# SP1_TYPEC_PWR_IN.net
KiCad netlist of a schematic drawn in Altium Designer
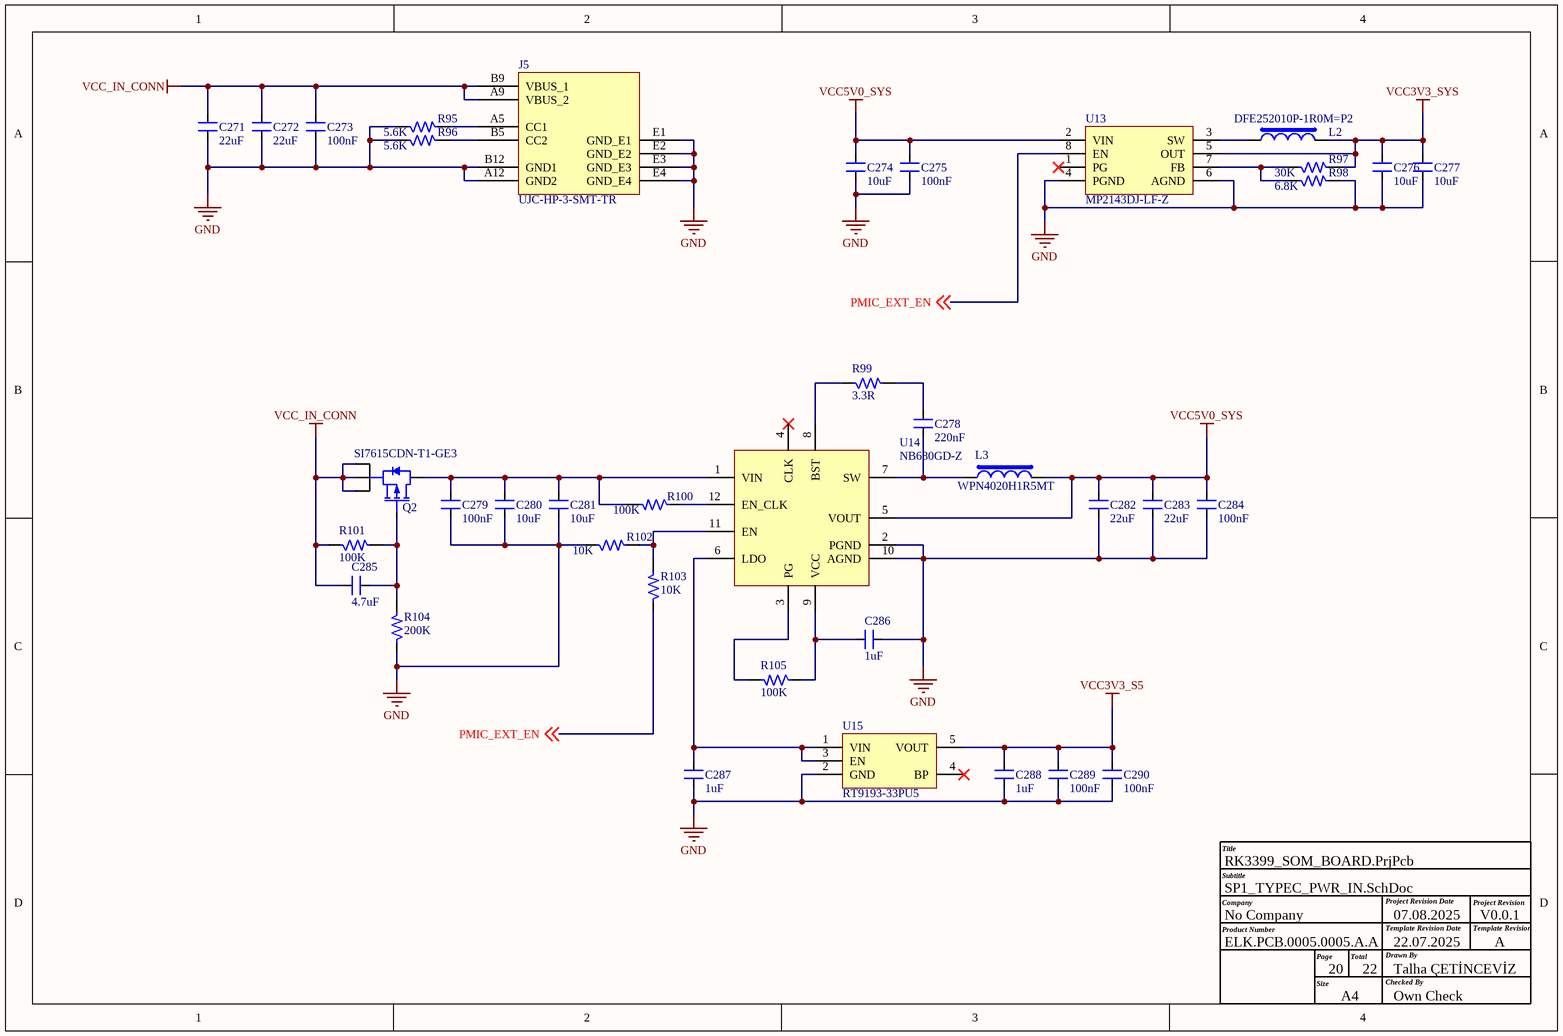
[diagram p0: SP1_TYPEC_PWR_IN.SchDoc]

(export (version "E")
  (design (tool "Eeschema 10.0.6"))
  (components
    (comp (ref "C271")
      (value "22uF")
      (footprint "CAP_0603")
      (description "22µF ±20% 10V Ceramic Capacitor X5R 0603 (1608 Metric)")
      (fields
        (field (name "MANUFACTURER") "Murata Electronics")
        (field (name "MANUFACTURER PART NUMBER") "GRM188R61A226ME15D")
      )
      (libsource (lib "EsteemPCB_SOM_Course_intlib") (part "CAP_22uF-10V-20%-0603"))
    )
    (comp (ref "C272")
      (value "22uF")
      (footprint "CAP_0603")
      (description "22µF ±20% 10V Ceramic Capacitor X5R 0603 (1608 Metric)")
      (fields
        (field (name "MANUFACTURER") "Murata Electronics")
        (field (name "MANUFACTURER PART NUMBER") "GRM188R61A226ME15D")
      )
      (libsource (lib "EsteemPCB_SOM_Course_intlib") (part "CAP_22uF-10V-20%-0603"))
    )
    (comp (ref "C273")
      (value "100nF")
      (footprint "CAP_0402")
      (description "0.1µF ±10% 25V Ceramic Capacitor X7R 0402 (1005 Metric)")
      (fields
        (field (name "MANUFACTURER") "Walsin Technology Corporation")
        (field (name "MANUFACTURER PART NUMBER") "0402B104K250CT")
      )
      (libsource (lib "EsteemPCB_SOM_Course_intlib") (part "CAP_100nF-25V-10%-0402"))
    )
    (comp (ref "C274")
      (value "10uF")
      (footprint "CAP_0402")
      (description "10µF ±20% 10V Ceramic Capacitor X5R 0402 (1005 Metric)")
      (fields
        (field (name "MANUFACTURER PART NUMBER") "CL05A106MP5NUNC")
        (field (name "MANUFACTURER") "Samsung Electro-Mechanics")
      )
      (libsource (lib "EsteemPCB_SOM_Course_intlib") (part "CAP_10uF-10V-20%-0402"))
    )
    (comp (ref "C275")
      (value "100nF")
      (footprint "CAP_0402")
      (description "0.1µF ±10% 25V Ceramic Capacitor X7R 0402 (1005 Metric)")
      (fields
        (field (name "MANUFACTURER") "Walsin Technology Corporation")
        (field (name "MANUFACTURER PART NUMBER") "0402B104K250CT")
      )
      (libsource (lib "EsteemPCB_SOM_Course_intlib") (part "CAP_100nF-25V-10%-0402"))
    )
    (comp (ref "C276")
      (value "10uF")
      (footprint "CAP_0402")
      (description "10µF ±20% 10V Ceramic Capacitor X5R 0402 (1005 Metric)")
      (fields
        (field (name "MANUFACTURER PART NUMBER") "CL05A106MP5NUNC")
        (field (name "MANUFACTURER") "Samsung Electro-Mechanics")
      )
      (libsource (lib "EsteemPCB_SOM_Course_intlib") (part "CAP_10uF-10V-20%-0402"))
    )
    (comp (ref "C277")
      (value "10uF")
      (footprint "CAP_0402")
      (description "10µF ±20% 10V Ceramic Capacitor X5R 0402 (1005 Metric)")
      (fields
        (field (name "MANUFACTURER PART NUMBER") "CL05A106MP5NUNC")
        (field (name "MANUFACTURER") "Samsung Electro-Mechanics")
      )
      (libsource (lib "EsteemPCB_SOM_Course_intlib") (part "CAP_10uF-10V-20%-0402"))
    )
    (comp (ref "C278")
      (value "220nF")
      (footprint "CAP_0402")
      (description "0.22µF ±10% 10V Ceramic Capacitor X7R 0402 (1005 Metric)")
      (fields
        (field (name "MANUFACTURER") "Samsung Electro-Mechanics")
        (field (name "MANUFACTURER PART NUMBER") "CL05B224KP5NNNC")
      )
      (libsource (lib "EsteemPCB_SOM_Course_intlib") (part "CAP_220nF-10V-10%-0402"))
    )
    (comp (ref "C279")
      (value "100nF")
      (footprint "CAP_0402")
      (description "0.1µF ±10% 25V Ceramic Capacitor X7R 0402 (1005 Metric)")
      (fields
        (field (name "MANUFACTURER") "Walsin Technology Corporation")
        (field (name "MANUFACTURER PART NUMBER") "0402B104K250CT")
      )
      (libsource (lib "EsteemPCB_SOM_Course_intlib") (part "CAP_100nF-25V-10%-0402"))
    )
    (comp (ref "C280")
      (value "10uF")
      (footprint "CAP_0402")
      (description "10µF ±20% 10V Ceramic Capacitor X5R 0402 (1005 Metric)")
      (fields
        (field (name "MANUFACTURER PART NUMBER") "CL05A106MP5NUNC")
        (field (name "MANUFACTURER") "Samsung Electro-Mechanics")
      )
      (libsource (lib "EsteemPCB_SOM_Course_intlib") (part "CAP_10uF-10V-20%-0402"))
    )
    (comp (ref "C281")
      (value "10uF")
      (footprint "CAP_0402")
      (description "10µF ±20% 10V Ceramic Capacitor X5R 0402 (1005 Metric)")
      (fields
        (field (name "MANUFACTURER PART NUMBER") "CL05A106MP5NUNC")
        (field (name "MANUFACTURER") "Samsung Electro-Mechanics")
      )
      (libsource (lib "EsteemPCB_SOM_Course_intlib") (part "CAP_10uF-10V-20%-0402"))
    )
    (comp (ref "C282")
      (value "22uF")
      (footprint "CAP_0603")
      (description "22µF ±20% 10V Ceramic Capacitor X5R 0603 (1608 Metric)")
      (fields
        (field (name "MANUFACTURER") "Murata Electronics")
        (field (name "MANUFACTURER PART NUMBER") "GRM188R61A226ME15D")
      )
      (libsource (lib "EsteemPCB_SOM_Course_intlib") (part "CAP_22uF-10V-20%-0603"))
    )
    (comp (ref "C283")
      (value "22uF")
      (footprint "CAP_0603")
      (description "22µF ±20% 10V Ceramic Capacitor X5R 0603 (1608 Metric)")
      (fields
        (field (name "MANUFACTURER") "Murata Electronics")
        (field (name "MANUFACTURER PART NUMBER") "GRM188R61A226ME15D")
      )
      (libsource (lib "EsteemPCB_SOM_Course_intlib") (part "CAP_22uF-10V-20%-0603"))
    )
    (comp (ref "C284")
      (value "100nF")
      (footprint "CAP_0402")
      (description "0.1µF ±10% 25V Ceramic Capacitor X7R 0402 (1005 Metric)")
      (fields
        (field (name "MANUFACTURER") "Walsin Technology Corporation")
        (field (name "MANUFACTURER PART NUMBER") "0402B104K250CT")
      )
      (libsource (lib "EsteemPCB_SOM_Course_intlib") (part "CAP_100nF-25V-10%-0402"))
    )
    (comp (ref "C285")
      (value "4.7uF")
      (footprint "CAP_0402")
      (description "4.7µF ±10% 10V Ceramic Capacitor X5R 0402 (1005 Metric)")
      (fields
        (field (name "MANUFACTURER") "Samsung Electro-Mechanics")
        (field (name "MANUFACTURER PART NUMBER") "CL05A475KP5NRNC")
      )
      (libsource (lib "EsteemPCB_SOM_Course_intlib") (part "CAP_4.7uF-10V-10%-0402"))
    )
    (comp (ref "C286")
      (value "1uF")
      (footprint "CAP_0402")
      (description "1µF ±10% 16V Ceramic Capacitor X5R 0402 (1005 Metric)")
      (fields
        (field (name "MANUFACTURER") "Knowles Novacap")
        (field (name "MANUFACTURER PART NUMBER") "0402BW105K160YT")
      )
      (libsource (lib "EsteemPCB_SOM_Course_intlib") (part "CAP_1uF-16V-10%-0402"))
    )
    (comp (ref "C287")
      (value "1uF")
      (footprint "CAP_0402")
      (description "1µF ±10% 16V Ceramic Capacitor X5R 0402 (1005 Metric)")
      (fields
        (field (name "MANUFACTURER") "Knowles Novacap")
        (field (name "MANUFACTURER PART NUMBER") "0402BW105K160YT")
      )
      (libsource (lib "EsteemPCB_SOM_Course_intlib") (part "CAP_1uF-16V-10%-0402"))
    )
    (comp (ref "C288")
      (value "1uF")
      (footprint "CAP_0402")
      (description "1µF ±10% 16V Ceramic Capacitor X5R 0402 (1005 Metric)")
      (fields
        (field (name "MANUFACTURER") "Knowles Novacap")
        (field (name "MANUFACTURER PART NUMBER") "0402BW105K160YT")
      )
      (libsource (lib "EsteemPCB_SOM_Course_intlib") (part "CAP_1uF-16V-10%-0402"))
    )
    (comp (ref "C289")
      (value "100nF")
      (footprint "CAP_0402")
      (description "0.1µF ±10% 25V Ceramic Capacitor X7R 0402 (1005 Metric)")
      (fields
        (field (name "MANUFACTURER") "Walsin Technology Corporation")
        (field (name "MANUFACTURER PART NUMBER") "0402B104K250CT")
      )
      (libsource (lib "EsteemPCB_SOM_Course_intlib") (part "CAP_100nF-25V-10%-0402"))
    )
    (comp (ref "C290")
      (value "100nF")
      (footprint "CAP_0402")
      (description "0.1µF ±10% 25V Ceramic Capacitor X7R 0402 (1005 Metric)")
      (fields
        (field (name "MANUFACTURER") "Walsin Technology Corporation")
        (field (name "MANUFACTURER PART NUMBER") "0402B104K250CT")
      )
      (libsource (lib "EsteemPCB_SOM_Course_intlib") (part "CAP_100nF-25V-10%-0402"))
    )
    (comp (ref "J5")
      (value "UJC-HP-3-SMT-TR")
      (footprint "CON6_48.4_UJC-HP-3-SMT-TR")
      (fields (field (name "MANUFACTURER") "CUI Devices"))
      (libsource (lib "EsteemPCB_SOM_Course_intlib") (part "CON-TYPEC_6X1-100-RA-TH"))
    )
    (comp (ref "L2")
      (value "DFE252010P-1R0M=P2")
      (footprint "IND_1008")
      (description "1µH Shielded Wirewound Inductor 3.8A 54mOhm Max 1008 (2520 Metric)")
      (fields (field (name "MANUFACTURER") "Murata Electronics"))
      (libsource (lib "EsteemPCB_SOM_Course_intlib") (part "IND_1uH-3.8A-20%-1008"))
    )
    (comp (ref "L3")
      (value "WPN4020H1R5MT")
      (footprint "IND_1616")
      (fields (field (name "MANUFACTURER") "Sunlord"))
      (libsource (lib "EsteemPCB_SOM_Course_intlib") (part "IND_1.5uH-6A-20%-SMD"))
    )
    (comp (ref "Q2")
      (value "SI7615CDN-T1-GE3")
      (footprint "PowerPAK_1212-8_SMD")
      (description "P-Channel 20V 35A (Tc) 33W (Tc) Surface Mount PowerPAK® 1212-8")
      (fields (field (name "MANUFACTURER") "Vishay Siliconix"))
      (libsource (lib "EsteemPCB_SOM_Course_intlib") (part "MOSFET-P_20V-35A-1212-8"))
    )
    (comp (ref "R95")
      (value "5.6K")
      (footprint "RES_0402")
      (fields
        (field (name "MANUFACTURER") "KOA Speer Electronics, Inc.")
        (field (name "MANUFACTURER PART NUMBER") "RK73H1ETTP5601F")
      )
      (libsource (lib "EsteemPCB_SOM_Course_intlib") (part "RES_5.6K-0.1W-1%-0402"))
    )
    (comp (ref "R96")
      (value "5.6K")
      (footprint "RES_0402")
      (fields
        (field (name "MANUFACTURER") "KOA Speer Electronics, Inc.")
        (field (name "MANUFACTURER PART NUMBER") "RK73H1ETTP5601F")
      )
      (libsource (lib "EsteemPCB_SOM_Course_intlib") (part "RES_5.6K-0.1W-1%-0402"))
    )
    (comp (ref "R97")
      (value "30K")
      (footprint "RES_0402")
      (fields
        (field (name "MANUFACTURER") "KOA Speer Electronics, Inc.")
        (field (name "MANUFACTURER PART NUMBER") "RK73H1ETTP3002F")
      )
      (libsource (lib "EsteemPCB_SOM_Course_intlib") (part "RES_30K-0.1W-1%-0402"))
    )
    (comp (ref "R98")
      (value "6.8K")
      (footprint "RES_0402")
      (description "6.8 kOhms ±1% 0.1W, 1/10W Chip Resistor 0402 (1005 Metric) Anti-Sulfur Thin Film")
      (fields
        (field (name "MANUFACTURER") "Vishay Beyschlag/Draloric/BC Components")
        (field (name "MANUFACTURER PART NUMBER") "MCS04020C6801FE000")
      )
      (libsource (lib "EsteemPCB_SOM_Course_intlib") (part "RES_6.8K-0.1W-1%-0402"))
    )
    (comp (ref "R99")
      (value "3.3R")
      (footprint "RES_0402")
      (fields
        (field (name "MANUFACTURER") "Panasonic Electronic Components")
        (field (name "MANUFACTURER PART NUMBER") "ERJ-U02F3R30X")
      )
      (libsource (lib "EsteemPCB_SOM_Course_intlib") (part "RES_3.3R-0.1W-1%-0402"))
    )
    (comp (ref "R100")
      (value "100K")
      (footprint "RES_0402")
      (description "100 kOhms ±1% 0.1W, 1/10W Chip Resistor 0402 (1005 Metric) Anti-Sulfur Thin Film")
      (fields
        (field (name "MANUFACTURER") "Vishay Beyschlag/Draloric/BC Components")
        (field (name "MANUFACTURER PART NUMBER") "MCS04020C1003FE000")
      )
      (libsource (lib "EsteemPCB_SOM_Course_intlib") (part "RES_100K-0.1W-1%-0402"))
    )
    (comp (ref "R101")
      (value "100K")
      (footprint "RES_0402")
      (description "100 kOhms ±1% 0.1W, 1/10W Chip Resistor 0402 (1005 Metric) Anti-Sulfur Thin Film")
      (fields
        (field (name "MANUFACTURER") "Vishay Beyschlag/Draloric/BC Components")
        (field (name "MANUFACTURER PART NUMBER") "MCS04020C1003FE000")
      )
      (libsource (lib "EsteemPCB_SOM_Course_intlib") (part "RES_100K-0.1W-1%-0402"))
    )
    (comp (ref "R102")
      (value "10K")
      (footprint "RES_0402")
      (description "10 kOhms ±1% 0.1W, 1/10W Chip Resistor 0402 (1005 Metric) Anti-Sulfur Thin Film")
      (fields
        (field (name "MANUFACTURER") "Vishay Beyschlag/Draloric/BC Components")
        (field (name "MANUFACTURER PART NUMBER") "MCS04020C1002FE000")
      )
      (libsource (lib "EsteemPCB_SOM_Course_intlib") (part "RES_10K-0.1W-1%-0402"))
    )
    (comp (ref "R103")
      (value "10K")
      (footprint "RES_0402")
      (description "10 kOhms ±1% 0.1W, 1/10W Chip Resistor 0402 (1005 Metric) Anti-Sulfur Thin Film")
      (fields
        (field (name "MANUFACTURER") "Vishay Beyschlag/Draloric/BC Components")
        (field (name "MANUFACTURER PART NUMBER") "MCS04020C1002FE000")
      )
      (libsource (lib "EsteemPCB_SOM_Course_intlib") (part "RES_10K-0.1W-1%-0402"))
    )
    (comp (ref "R104")
      (value "200K")
      (footprint "RES_0402")
      (description "200 kOhms ±1% 0.1W, 1/10W Chip Resistor 0402 (1005 Metric) Automotive AEC-Q200 Thick Film")
      (fields
        (field (name "MANUFACTURER") "Panasonic Electronic Components")
        (field (name "MANUFACTURER PART NUMBER") "ERJ-2RKF2003X")
      )
      (libsource (lib "EsteemPCB_SOM_Course_intlib") (part "RES_200K-0.1W-1%-0402"))
    )
    (comp (ref "R105")
      (value "100K")
      (footprint "RES_0402")
      (description "100 kOhms ±1% 0.1W, 1/10W Chip Resistor 0402 (1005 Metric) Anti-Sulfur Thin Film")
      (fields
        (field (name "MANUFACTURER") "Vishay Beyschlag/Draloric/BC Components")
        (field (name "MANUFACTURER PART NUMBER") "MCS04020C1003FE000")
      )
      (libsource (lib "EsteemPCB_SOM_Course_intlib") (part "RES_100K-0.1W-1%-0402"))
    )
    (comp (ref "U13")
      (value "MP2143DJ-LF-Z")
      (footprint "SOT23-8")
      (description "Switching Voltage Regulators 3A, 5.5V, 1.2MHz Sync Stp-Dwn Swtchr")
      (fields (field (name "MANUFACTURER") "Monolithic Power Systems (MPS)"))
      (libsource (lib "EsteemPCB_SOM_Course_intlib") (part "REG_0.6~5V-5.5V-3A-TSOT-23-8"))
    )
    (comp (ref "U14")
      (value "NB680GD-Z")
      (footprint "QFN-12_19_118X118_SMD")
      (description "Switching Voltage Regulators 26V Fixed 3.3 V-8A Sync Buck Converter")
      (fields (field (name "MANUFACTURER") "Monolithic Power Systems (MPS)"))
      (libsource (lib "EsteemPCB_SOM_Course_intlib") (part "REG_3.3V-26V-8A-QFN-12"))
    )
    (comp (ref "U15")
      (value "RT9193-33PU5")
      (footprint "SC70-5")
      (description "SC-70-5 Dropout Regulators(LDO) RoHS")
      (fields (field (name "MANUFACTURER") "Richtek Tech"))
      (libsource (lib "EsteemPCB_SOM_Course_intlib") (part "REG_3.3V-5.5V-300mA-SC-70-5"))
    )
  )
  (nets
    (net (code "1") (name "GND") (class "Default")
      (node (ref "C271") (pin "1") (pinfunction "1_1") (pintype "passive"))
      (node (ref "C272") (pin "1") (pinfunction "1_1") (pintype "passive"))
      (node (ref "C273") (pin "1") (pinfunction "1_1") (pintype "passive"))
      (node (ref "C274") (pin "1") (pinfunction "1_1") (pintype "passive"))
      (node (ref "C275") (pin "1") (pinfunction "1_1") (pintype "passive"))
      (node (ref "C276") (pin "1") (pinfunction "1_1") (pintype "passive"))
      (node (ref "C277") (pin "1") (pinfunction "1_1") (pintype "passive"))
      (node (ref "C279") (pin "1") (pinfunction "1_1") (pintype "passive"))
      (node (ref "C280") (pin "1") (pinfunction "1_1") (pintype "passive"))
      (node (ref "C281") (pin "1") (pinfunction "1_1") (pintype "passive"))
      (node (ref "C282") (pin "1") (pinfunction "1_1") (pintype "passive"))
      (node (ref "C283") (pin "1") (pinfunction "1_1") (pintype "passive"))
      (node (ref "C284") (pin "1") (pinfunction "1_1") (pintype "passive"))
      (node (ref "C286") (pin "1") (pinfunction "1_1") (pintype "passive"))
      (node (ref "C287") (pin "1") (pinfunction "1_1") (pintype "passive"))
      (node (ref "C288") (pin "1") (pinfunction "1_1") (pintype "passive"))
      (node (ref "C289") (pin "1") (pinfunction "1_1") (pintype "passive"))
      (node (ref "C290") (pin "1") (pinfunction "1_1") (pintype "passive"))
      (node (ref "J5") (pin "A12") (pinfunction "GND2_A12") (pintype "passive"))
      (node (ref "J5") (pin "B12") (pinfunction "GND1_B12") (pintype "passive"))
      (node (ref "J5") (pin "E1") (pinfunction "GND_E1_E1") (pintype "passive"))
      (node (ref "J5") (pin "E2") (pinfunction "GND_E2_E2") (pintype "passive"))
      (node (ref "J5") (pin "E3") (pinfunction "GND_E3_E3") (pintype "passive"))
      (node (ref "J5") (pin "E4") (pinfunction "GND_E4_E4") (pintype "passive"))
      (node (ref "R102") (pin "1") (pinfunction "1_1") (pintype "passive"))
      (node (ref "R104") (pin "1") (pinfunction "1_1") (pintype "passive"))
      (node (ref "R95") (pin "1") (pinfunction "1_1") (pintype "passive"))
      (node (ref "R96") (pin "1") (pinfunction "1_1") (pintype "passive"))
      (node (ref "R98") (pin "2") (pinfunction "2_2") (pintype "passive"))
      (node (ref "U13") (pin "4") (pinfunction "PGND_4") (pintype "passive"))
      (node (ref "U13") (pin "6") (pinfunction "AGND_6") (pintype "passive"))
      (node (ref "U14") (pin "10") (pinfunction "AGND_10") (pintype "passive"))
      (node (ref "U14") (pin "2") (pinfunction "PGND_2") (pintype "passive"))
      (node (ref "U15") (pin "2") (pinfunction "GND_2") (pintype "passive"))
    )
    (net (code "2") (name "Net-(C278-Pad2)") (class "Default")
      (node (ref "C278") (pin "2") (pinfunction "2_2") (pintype "passive"))
      (node (ref "R99") (pin "2") (pinfunction "2_2") (pintype "passive"))
    )
    (net (code "3") (name "Net-(J5-CC1)") (class "Default")
      (node (ref "J5") (pin "A5") (pinfunction "CC1_A5") (pintype "passive"))
      (node (ref "R95") (pin "2") (pinfunction "2_2") (pintype "passive"))
    )
    (net (code "4") (name "Net-(J5-CC2)") (class "Default")
      (node (ref "J5") (pin "B5") (pinfunction "CC2_B5") (pintype "passive"))
      (node (ref "R96") (pin "2") (pinfunction "2_2") (pintype "passive"))
    )
    (net (code "5") (name "Net-(Q2-D)") (class "Default")
      (node (ref "C279") (pin "2") (pinfunction "2_2") (pintype "passive"))
      (node (ref "C280") (pin "2") (pinfunction "2_2") (pintype "passive"))
      (node (ref "C281") (pin "2") (pinfunction "2_2") (pintype "passive"))
      (node (ref "Q2") (pin "5") (pinfunction "D_5") (pintype "passive"))
      (node (ref "R100") (pin "2") (pinfunction "2_2") (pintype "passive"))
      (node (ref "U14") (pin "1") (pinfunction "VIN_1") (pintype "passive"))
    )
    (net (code "6") (name "Net-(Q2-G)") (class "Default")
      (node (ref "C285") (pin "2") (pinfunction "2_2") (pintype "passive"))
      (node (ref "Q2") (pin "4") (pinfunction "G_4") (pintype "passive"))
      (node (ref "R101") (pin "2") (pinfunction "2_2") (pintype "passive"))
      (node (ref "R104") (pin "2") (pinfunction "2_2") (pintype "passive"))
    )
    (net (code "7") (name "Net-(U13-FB)") (class "Default")
      (node (ref "R97") (pin "1") (pinfunction "1_1") (pintype "passive"))
      (node (ref "R98") (pin "1") (pinfunction "1_1") (pintype "passive"))
      (node (ref "U13") (pin "7") (pinfunction "FB_7") (pintype "passive"))
    )
    (net (code "8") (name "Net-(U13-SW)") (class "Default")
      (node (ref "L2") (pin "1") (pinfunction "1_1") (pintype "passive"))
      (node (ref "U13") (pin "3") (pinfunction "SW_3") (pintype "passive"))
    )
    (net (code "9") (name "Net-(U14-BST)") (class "Default")
      (node (ref "R99") (pin "1") (pinfunction "1_1") (pintype "passive"))
      (node (ref "U14") (pin "8") (pinfunction "BST_8") (pintype "passive"))
    )
    (net (code "10") (name "Net-(U14-EN)") (class "Default")
      (node (ref "R102") (pin "2") (pinfunction "2_2") (pintype "passive"))
      (node (ref "R103") (pin "2") (pinfunction "2_2") (pintype "passive"))
      (node (ref "U14") (pin "11") (pinfunction "EN_11") (pintype "passive"))
    )
    (net (code "11") (name "Net-(U14-EN_CLK)") (class "Default")
      (node (ref "R100") (pin "1") (pinfunction "1_1") (pintype "passive"))
      (node (ref "U14") (pin "12") (pinfunction "EN_CLK_12") (pintype "passive"))
    )
    (net (code "12") (name "Net-(U14-LDO)") (class "Default")
      (node (ref "C287") (pin "2") (pinfunction "2_2") (pintype "passive"))
      (node (ref "U14") (pin "6") (pinfunction "LDO_6") (pintype "passive"))
      (node (ref "U15") (pin "1") (pinfunction "VIN_1") (pintype "passive"))
      (node (ref "U15") (pin "3") (pinfunction "EN_3") (pintype "passive"))
    )
    (net (code "13") (name "Net-(U14-PG)") (class "Default")
      (node (ref "R105") (pin "2") (pinfunction "2_2") (pintype "passive"))
      (node (ref "U14") (pin "3") (pinfunction "PG_3") (pintype "passive"))
    )
    (net (code "14") (name "Net-(U14-SW)") (class "Default")
      (node (ref "C278") (pin "1") (pinfunction "1_1") (pintype "passive"))
      (node (ref "L3") (pin "1") (pinfunction "1_1") (pintype "passive"))
      (node (ref "U14") (pin "7") (pinfunction "SW_7") (pintype "passive"))
    )
    (net (code "15") (name "Net-(U14-VCC)") (class "Default")
      (node (ref "C286") (pin "2") (pinfunction "2_2") (pintype "passive"))
      (node (ref "R105") (pin "1") (pinfunction "1_1") (pintype "passive"))
      (node (ref "U14") (pin "9") (pinfunction "VCC_9") (pintype "passive"))
    )
    (net (code "16") (name "PMIC_EXT_EN") (class "Default")
      (node (ref "R103") (pin "1") (pinfunction "1_1") (pintype "passive"))
      (node (ref "U13") (pin "8") (pinfunction "EN_8") (pintype "passive"))
    )
    (net (code "17") (name "VCC3V3_S5") (class "Default")
      (node (ref "C288") (pin "2") (pinfunction "2_2") (pintype "passive"))
      (node (ref "C289") (pin "2") (pinfunction "2_2") (pintype "passive"))
      (node (ref "C290") (pin "2") (pinfunction "2_2") (pintype "passive"))
      (node (ref "U15") (pin "5") (pinfunction "VOUT_5") (pintype "passive"))
    )
    (net (code "18") (name "VCC3V3_SYS") (class "Default")
      (node (ref "C276") (pin "2") (pinfunction "2_2") (pintype "passive"))
      (node (ref "C277") (pin "2") (pinfunction "2_2") (pintype "passive"))
      (node (ref "L2") (pin "2") (pinfunction "2_2") (pintype "passive"))
      (node (ref "R97") (pin "2") (pinfunction "2_2") (pintype "passive"))
      (node (ref "U13") (pin "5") (pinfunction "OUT_5") (pintype "passive"))
    )
    (net (code "19") (name "VCC5V0_SYS") (class "Default")
      (node (ref "C274") (pin "2") (pinfunction "2_2") (pintype "passive"))
      (node (ref "C275") (pin "2") (pinfunction "2_2") (pintype "passive"))
      (node (ref "C282") (pin "2") (pinfunction "2_2") (pintype "passive"))
      (node (ref "C283") (pin "2") (pinfunction "2_2") (pintype "passive"))
      (node (ref "C284") (pin "2") (pinfunction "2_2") (pintype "passive"))
      (node (ref "L3") (pin "2") (pinfunction "2_2") (pintype "passive"))
      (node (ref "U13") (pin "2") (pinfunction "VIN_2") (pintype "passive"))
      (node (ref "U14") (pin "5") (pinfunction "VOUT_5") (pintype "passive"))
    )
    (net (code "20") (name "VCC_IN_CONN") (class "Default")
      (node (ref "C271") (pin "2") (pinfunction "2_2") (pintype "passive"))
      (node (ref "C272") (pin "2") (pinfunction "2_2") (pintype "passive"))
      (node (ref "C273") (pin "2") (pinfunction "2_2") (pintype "passive"))
      (node (ref "C285") (pin "1") (pinfunction "1_1") (pintype "passive"))
      (node (ref "J5") (pin "A9") (pinfunction "VBUS_2_A9") (pintype "passive"))
      (node (ref "J5") (pin "B9") (pinfunction "VBUS_1_B9") (pintype "passive"))
      (node (ref "Q2") (pin "1") (pinfunction "S_1") (pintype "passive"))
      (node (ref "Q2") (pin "2") (pinfunction "S_2") (pintype "passive"))
      (node (ref "Q2") (pin "3") (pinfunction "S_3") (pintype "passive"))
      (node (ref "R101") (pin "1") (pinfunction "1_1") (pintype "passive"))
    )
    (net (code "21") (name "unconnected-(U13-PG-Pad1)") (class "Default")
      (node (ref "U13") (pin "1") (pinfunction "PG_1") (pintype "passive+no_connect"))
    )
    (net (code "22") (name "unconnected-(U14-CLK-Pad4)") (class "Default")
      (node (ref "U14") (pin "4") (pinfunction "CLK_4") (pintype "passive+no_connect"))
    )
    (net (code "23") (name "unconnected-(U15-BP-Pad4)") (class "Default")
      (node (ref "U15") (pin "4") (pinfunction "BP_4") (pintype "passive+no_connect"))
    )
  )
)
